# CNCMachineV1.net
KiCad netlist of a schematic drawn in EAGLE
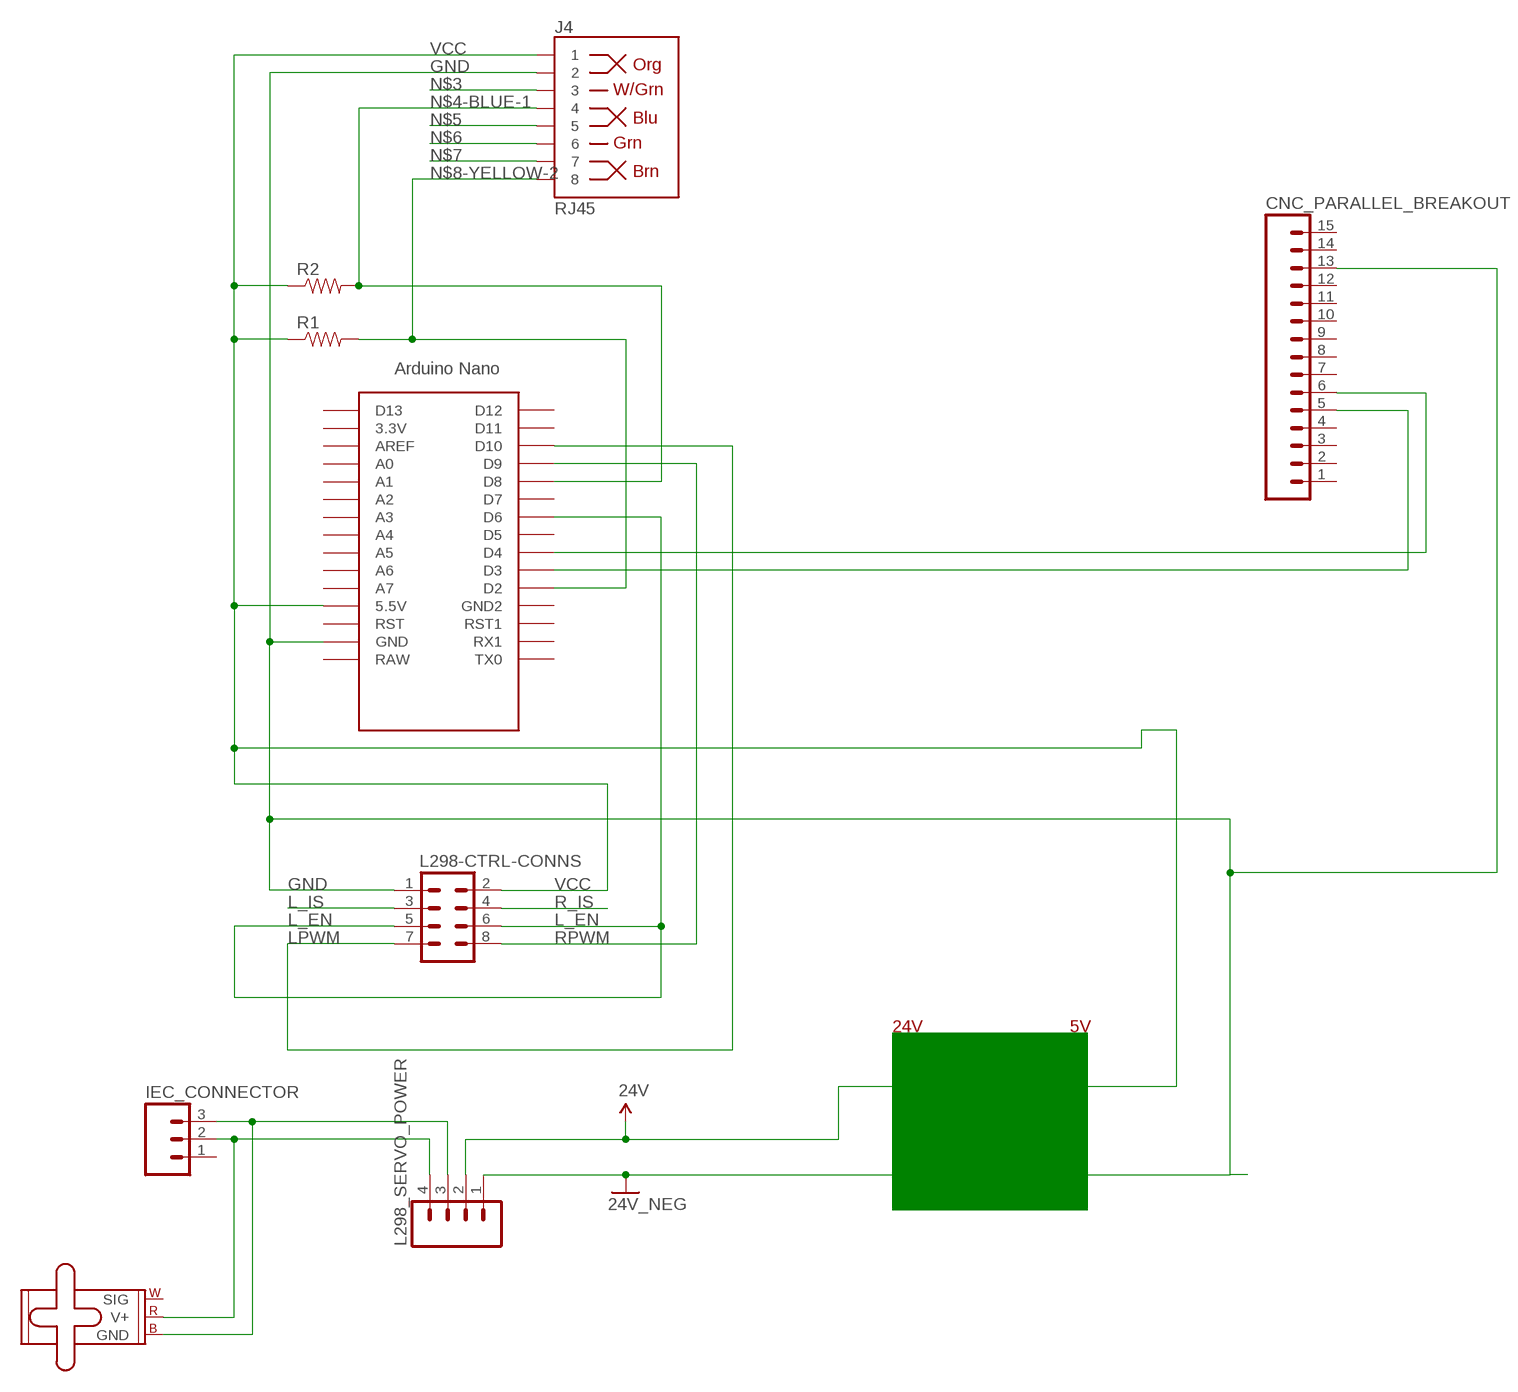
[diagram p0: schematic, sheet 1]

(export (version "E")
  (design (tool "Eeschema 10.0.6"))
  (components
    (comp (ref "CNC_PARALLEL_BREAKOUT")
      (value "M15")
      (footprint "eagle-import:1X15")
      (libsource (lib "eagle-import") (part "M15"))
    )
    (comp (ref "IEC_CONNECTOR")
      (value "M03-SCREW-5MM")
      (footprint "eagle-import:SCREWTERMINAL-5MM-3")
      (libsource (lib "eagle-import") (part "M03-SCREW-5MM"))
    )
    (comp (ref "J4")
      (value "RJ45")
      (footprint "eagle-import:RJ45-8")
      (libsource (lib "eagle-import") (part "RJ45-8PTH"))
    )
    (comp (ref "L298-CTRL-CONNS")
      (value "M04X2")
      (footprint "eagle-import:2X4")
      (libsource (lib "eagle-import") (part "M04X2"))
    )
    (comp (ref "L298_SERVO_POWER")
      (value "M04SCREW")
      (footprint "eagle-import:SCREWTERMINAL-3.5MM-4")
      (libsource (lib "eagle-import") (part "M04SCREW"))
    )
    (comp (ref "M1")
      (value "SMALL_SERVO")
      (footprint "eagle-import:1X03")
      (libsource (lib "eagle-import") (part "SMALL_SERVO"))
    )
    (comp (ref "R1")
      (value "RESISTORPTH-1/2W")
      (footprint "eagle-import:AXIAL-0.5")
      (libsource (lib "eagle-import") (part "RESISTORPTH-1/2W"))
    )
    (comp (ref "R2")
      (value "RESISTORPTH-1/2W")
      (footprint "eagle-import:AXIAL-0.5")
      (libsource (lib "eagle-import") (part "RESISTORPTH-1/2W"))
    )
    (comp (ref "U$1")
      (value "NANO")
      (footprint "eagle-import:NANO")
      (libsource (lib "eagle-import") (part "NANO"))
    )
  )
  (nets
    (net (code "1") (name "/LPWM") (class "Default")
      (node (ref "L298-CTRL-CONNS") (pin "7") (pinfunction "7_7") (pintype "passive"))
      (node (ref "U$1") (pin "D10") (pinfunction "D10_D10") (pintype "bidirectional"))
    )
    (net (code "2") (name "/L_EN") (class "Default")
      (node (ref "L298-CTRL-CONNS") (pin "5") (pinfunction "5_5") (pintype "passive"))
      (node (ref "L298-CTRL-CONNS") (pin "6") (pinfunction "6_6") (pintype "passive"))
      (node (ref "U$1") (pin "D6") (pinfunction "D6_D6") (pintype "bidirectional"))
    )
    (net (code "3") (name "/L_IS") (class "Default")
      (node (ref "L298-CTRL-CONNS") (pin "3") (pinfunction "3_3") (pintype "passive"))
    )
    (net (code "4") (name "/N$3") (class "Default")
      (node (ref "J4") (pin "3") (pinfunction "3_3") (pintype "bidirectional"))
    )
    (net (code "5") (name "/N$4-BLUE-1") (class "Default")
      (node (ref "J4") (pin "4") (pinfunction "4_4") (pintype "bidirectional"))
      (node (ref "R2") (pin "P$2") (pinfunction "2_P$2") (pintype "passive"))
      (node (ref "U$1") (pin "D8") (pinfunction "D8_D8") (pintype "bidirectional"))
    )
    (net (code "6") (name "/N$5") (class "Default")
      (node (ref "J4") (pin "5") (pinfunction "5_5") (pintype "bidirectional"))
    )
    (net (code "7") (name "/N$6") (class "Default")
      (node (ref "J4") (pin "6") (pinfunction "6_6") (pintype "bidirectional"))
    )
    (net (code "8") (name "/N$7") (class "Default")
      (node (ref "J4") (pin "7") (pinfunction "7_7") (pintype "bidirectional"))
    )
    (net (code "9") (name "/N$8-YELLOW-2") (class "Default")
      (node (ref "J4") (pin "8") (pinfunction "8_8") (pintype "bidirectional"))
      (node (ref "R1") (pin "P$2") (pinfunction "2_P$2") (pintype "passive"))
      (node (ref "U$1") (pin "D2") (pinfunction "D2_D2") (pintype "bidirectional"))
    )
    (net (code "10") (name "/RPWM") (class "Default")
      (node (ref "L298-CTRL-CONNS") (pin "8") (pinfunction "8_8") (pintype "passive"))
      (node (ref "U$1") (pin "D9") (pinfunction "D9_D9") (pintype "bidirectional"))
    )
    (net (code "11") (name "/R_IS") (class "Default")
      (node (ref "L298-CTRL-CONNS") (pin "4") (pinfunction "4_4") (pintype "passive"))
    )
    (net (code "12") (name "24V") (class "Default")
      (node (ref "J4") (pin "1") (pinfunction "1_1") (pintype "bidirectional"))
      (node (ref "L298-CTRL-CONNS") (pin "2") (pinfunction "2_2") (pintype "passive"))
      (node (ref "L298_SERVO_POWER") (pin "2") (pinfunction "2_2") (pintype "passive"))
      (node (ref "R1") (pin "P$1") (pinfunction "1_P$1") (pintype "passive"))
      (node (ref "R2") (pin "P$1") (pinfunction "1_P$1") (pintype "passive"))
      (node (ref "U$1") (pin "5V") (pinfunction "5.5V_5V") (pintype "bidirectional"))
    )
    (net (code "13") (name "24V_NEG") (class "Default")
      (node (ref "CNC_PARALLEL_BREAKOUT") (pin "13") (pinfunction "13_13") (pintype "passive"))
      (node (ref "J4") (pin "2") (pinfunction "2_2") (pintype "bidirectional"))
      (node (ref "L298-CTRL-CONNS") (pin "1") (pinfunction "1_1") (pintype "passive"))
      (node (ref "L298_SERVO_POWER") (pin "1") (pinfunction "1_1") (pintype "passive"))
      (node (ref "U$1") (pin "GND") (pinfunction "GND_GND") (pintype "bidirectional"))
    )
    (net (code "14") (name "Net-(CNC_PARALLEL_BREAKOUT-Pad5)") (class "Default")
      (node (ref "CNC_PARALLEL_BREAKOUT") (pin "5") (pinfunction "5_5") (pintype "passive"))
      (node (ref "U$1") (pin "D3") (pinfunction "D3_D3") (pintype "bidirectional"))
    )
    (net (code "15") (name "Net-(CNC_PARALLEL_BREAKOUT-Pad6)") (class "Default")
      (node (ref "CNC_PARALLEL_BREAKOUT") (pin "6") (pinfunction "6_6") (pintype "passive"))
      (node (ref "U$1") (pin "D4") (pinfunction "D4_D4") (pintype "bidirectional"))
    )
    (net (code "16") (name "Net-(M1-GND)") (class "Default")
      (node (ref "IEC_CONNECTOR") (pin "3") (pinfunction "3_3") (pintype "passive"))
      (node (ref "L298_SERVO_POWER") (pin "3") (pinfunction "3_3") (pintype "passive"))
      (node (ref "M1") (pin "3") (pinfunction "GND_3") (pintype "bidirectional"))
    )
    (net (code "17") (name "Net-(M1-V+)") (class "Default")
      (node (ref "IEC_CONNECTOR") (pin "2") (pinfunction "2_2") (pintype "passive"))
      (node (ref "L298_SERVO_POWER") (pin "4") (pinfunction "4_4") (pintype "passive"))
      (node (ref "M1") (pin "2") (pinfunction "V+_2") (pintype "bidirectional"))
    )
    (net (code "18") (name "unconnected-(CNC_PARALLEL_BREAKOUT-Pad1)") (class "Default")
      (node (ref "CNC_PARALLEL_BREAKOUT") (pin "1") (pinfunction "1_1") (pintype "passive"))
    )
    (net (code "19") (name "unconnected-(CNC_PARALLEL_BREAKOUT-Pad2)") (class "Default")
      (node (ref "CNC_PARALLEL_BREAKOUT") (pin "2") (pinfunction "2_2") (pintype "passive"))
    )
    (net (code "20") (name "unconnected-(CNC_PARALLEL_BREAKOUT-Pad3)") (class "Default")
      (node (ref "CNC_PARALLEL_BREAKOUT") (pin "3") (pinfunction "3_3") (pintype "passive"))
    )
    (net (code "21") (name "unconnected-(CNC_PARALLEL_BREAKOUT-Pad4)") (class "Default")
      (node (ref "CNC_PARALLEL_BREAKOUT") (pin "4") (pinfunction "4_4") (pintype "passive"))
    )
    (net (code "22") (name "unconnected-(CNC_PARALLEL_BREAKOUT-Pad7)") (class "Default")
      (node (ref "CNC_PARALLEL_BREAKOUT") (pin "7") (pinfunction "7_7") (pintype "passive"))
    )
    (net (code "23") (name "unconnected-(CNC_PARALLEL_BREAKOUT-Pad8)") (class "Default")
      (node (ref "CNC_PARALLEL_BREAKOUT") (pin "8") (pinfunction "8_8") (pintype "passive"))
    )
    (net (code "24") (name "unconnected-(CNC_PARALLEL_BREAKOUT-Pad9)") (class "Default")
      (node (ref "CNC_PARALLEL_BREAKOUT") (pin "9") (pinfunction "9_9") (pintype "passive"))
    )
    (net (code "25") (name "unconnected-(CNC_PARALLEL_BREAKOUT-Pad10)") (class "Default")
      (node (ref "CNC_PARALLEL_BREAKOUT") (pin "10") (pinfunction "10_10") (pintype "passive"))
    )
    (net (code "26") (name "unconnected-(CNC_PARALLEL_BREAKOUT-Pad11)") (class "Default")
      (node (ref "CNC_PARALLEL_BREAKOUT") (pin "11") (pinfunction "11_11") (pintype "passive"))
    )
    (net (code "27") (name "unconnected-(CNC_PARALLEL_BREAKOUT-Pad12)") (class "Default")
      (node (ref "CNC_PARALLEL_BREAKOUT") (pin "12") (pinfunction "12_12") (pintype "passive"))
    )
    (net (code "28") (name "unconnected-(CNC_PARALLEL_BREAKOUT-Pad14)") (class "Default")
      (node (ref "CNC_PARALLEL_BREAKOUT") (pin "14") (pinfunction "14_14") (pintype "passive"))
    )
    (net (code "29") (name "unconnected-(CNC_PARALLEL_BREAKOUT-Pad15)") (class "Default")
      (node (ref "CNC_PARALLEL_BREAKOUT") (pin "15") (pinfunction "15_15") (pintype "passive"))
    )
    (net (code "30") (name "unconnected-(IEC_CONNECTOR-Pad1)") (class "Default")
      (node (ref "IEC_CONNECTOR") (pin "1") (pinfunction "1_1") (pintype "passive"))
    )
    (net (code "31") (name "unconnected-(M1-SIG-Pad1)") (class "Default")
      (node (ref "M1") (pin "1") (pinfunction "SIG_1") (pintype "bidirectional"))
    )
    (net (code "32") (name "unconnected-(U$1-GND2-PadGND1)") (class "Default")
      (node (ref "U$1") (pin "GND1") (pinfunction "GND2_GND1") (pintype "bidirectional"))
    )
    (net (code "33") (name "unconnected-(U$1-Pad3.3V)") (class "Default")
      (node (ref "U$1") (pin "3.3V") (pinfunction "3.3V_3.3V") (pintype "bidirectional"))
    )
    (net (code "34") (name "unconnected-(U$1-PadA0)") (class "Default")
      (node (ref "U$1") (pin "A0") (pinfunction "A0_A0") (pintype "bidirectional"))
    )
    (net (code "35") (name "unconnected-(U$1-PadA1)") (class "Default")
      (node (ref "U$1") (pin "A1") (pinfunction "A1_A1") (pintype "bidirectional"))
    )
    (net (code "36") (name "unconnected-(U$1-PadA2)") (class "Default")
      (node (ref "U$1") (pin "A2") (pinfunction "A2_A2") (pintype "bidirectional"))
    )
    (net (code "37") (name "unconnected-(U$1-PadA3)") (class "Default")
      (node (ref "U$1") (pin "A3") (pinfunction "A3_A3") (pintype "bidirectional"))
    )
    (net (code "38") (name "unconnected-(U$1-PadA4)") (class "Default")
      (node (ref "U$1") (pin "A4") (pinfunction "A4_A4") (pintype "bidirectional"))
    )
    (net (code "39") (name "unconnected-(U$1-PadA5)") (class "Default")
      (node (ref "U$1") (pin "A5") (pinfunction "A5_A5") (pintype "bidirectional"))
    )
    (net (code "40") (name "unconnected-(U$1-PadA6)") (class "Default")
      (node (ref "U$1") (pin "A6") (pinfunction "A6_A6") (pintype "bidirectional"))
    )
    (net (code "41") (name "unconnected-(U$1-PadA7)") (class "Default")
      (node (ref "U$1") (pin "A7") (pinfunction "A7_A7") (pintype "bidirectional"))
    )
    (net (code "42") (name "unconnected-(U$1-PadAREF)") (class "Default")
      (node (ref "U$1") (pin "AREF") (pinfunction "AREF_AREF") (pintype "bidirectional"))
    )
    (net (code "43") (name "unconnected-(U$1-PadD5)") (class "Default")
      (node (ref "U$1") (pin "D5") (pinfunction "D5_D5") (pintype "bidirectional"))
    )
    (net (code "44") (name "unconnected-(U$1-PadD7)") (class "Default")
      (node (ref "U$1") (pin "D7") (pinfunction "D7_D7") (pintype "bidirectional"))
    )
    (net (code "45") (name "unconnected-(U$1-PadD11)") (class "Default")
      (node (ref "U$1") (pin "D11") (pinfunction "D11_D11") (pintype "bidirectional"))
    )
    (net (code "46") (name "unconnected-(U$1-PadD12)") (class "Default")
      (node (ref "U$1") (pin "D12") (pinfunction "D12_D12") (pintype "bidirectional"))
    )
    (net (code "47") (name "unconnected-(U$1-PadD13)") (class "Default")
      (node (ref "U$1") (pin "D13") (pinfunction "D13_D13") (pintype "bidirectional"))
    )
    (net (code "48") (name "unconnected-(U$1-PadICSP1)") (class "Default")
      (node (ref "U$1") (pin "ICSP1") (pinfunction "ICSP1_ICSP1") (pintype "bidirectional"))
    )
    (net (code "49") (name "unconnected-(U$1-PadICSP2)") (class "Default")
      (node (ref "U$1") (pin "ICSP2") (pinfunction "ICSP2_ICSP2") (pintype "bidirectional"))
    )
    (net (code "50") (name "unconnected-(U$1-PadICSP3)") (class "Default")
      (node (ref "U$1") (pin "ICSP3") (pinfunction "ICSP3_ICSP3") (pintype "bidirectional"))
    )
    (net (code "51") (name "unconnected-(U$1-PadICSP4)") (class "Default")
      (node (ref "U$1") (pin "ICSP4") (pinfunction "ICSP4_ICSP4") (pintype "bidirectional"))
    )
    (net (code "52") (name "unconnected-(U$1-PadICSP5)") (class "Default")
      (node (ref "U$1") (pin "ICSP5") (pinfunction "ICSP5_ICSP5") (pintype "bidirectional"))
    )
    (net (code "53") (name "unconnected-(U$1-PadICSP6)") (class "Default")
      (node (ref "U$1") (pin "ICSP6") (pinfunction "ICSP6_ICSP6") (pintype "bidirectional"))
    )
    (net (code "54") (name "unconnected-(U$1-PadRAW)") (class "Default")
      (node (ref "U$1") (pin "RAW") (pinfunction "RAW_RAW") (pintype "bidirectional"))
    )
    (net (code "55") (name "unconnected-(U$1-PadRST)") (class "Default")
      (node (ref "U$1") (pin "RST") (pinfunction "RST_RST") (pintype "bidirectional"))
    )
    (net (code "56") (name "unconnected-(U$1-PadRST1)") (class "Default")
      (node (ref "U$1") (pin "RST1") (pinfunction "RST1_RST1") (pintype "bidirectional"))
    )
    (net (code "57") (name "unconnected-(U$1-PadRX1)") (class "Default")
      (node (ref "U$1") (pin "RX1") (pinfunction "RX1_RX1") (pintype "bidirectional"))
    )
    (net (code "58") (name "unconnected-(U$1-PadTX0)") (class "Default")
      (node (ref "U$1") (pin "TX0") (pinfunction "TX0_TX0") (pintype "bidirectional"))
    )
  )
)
